# oscillation.net
KiCad netlist of a schematic drawn in Altium Designer
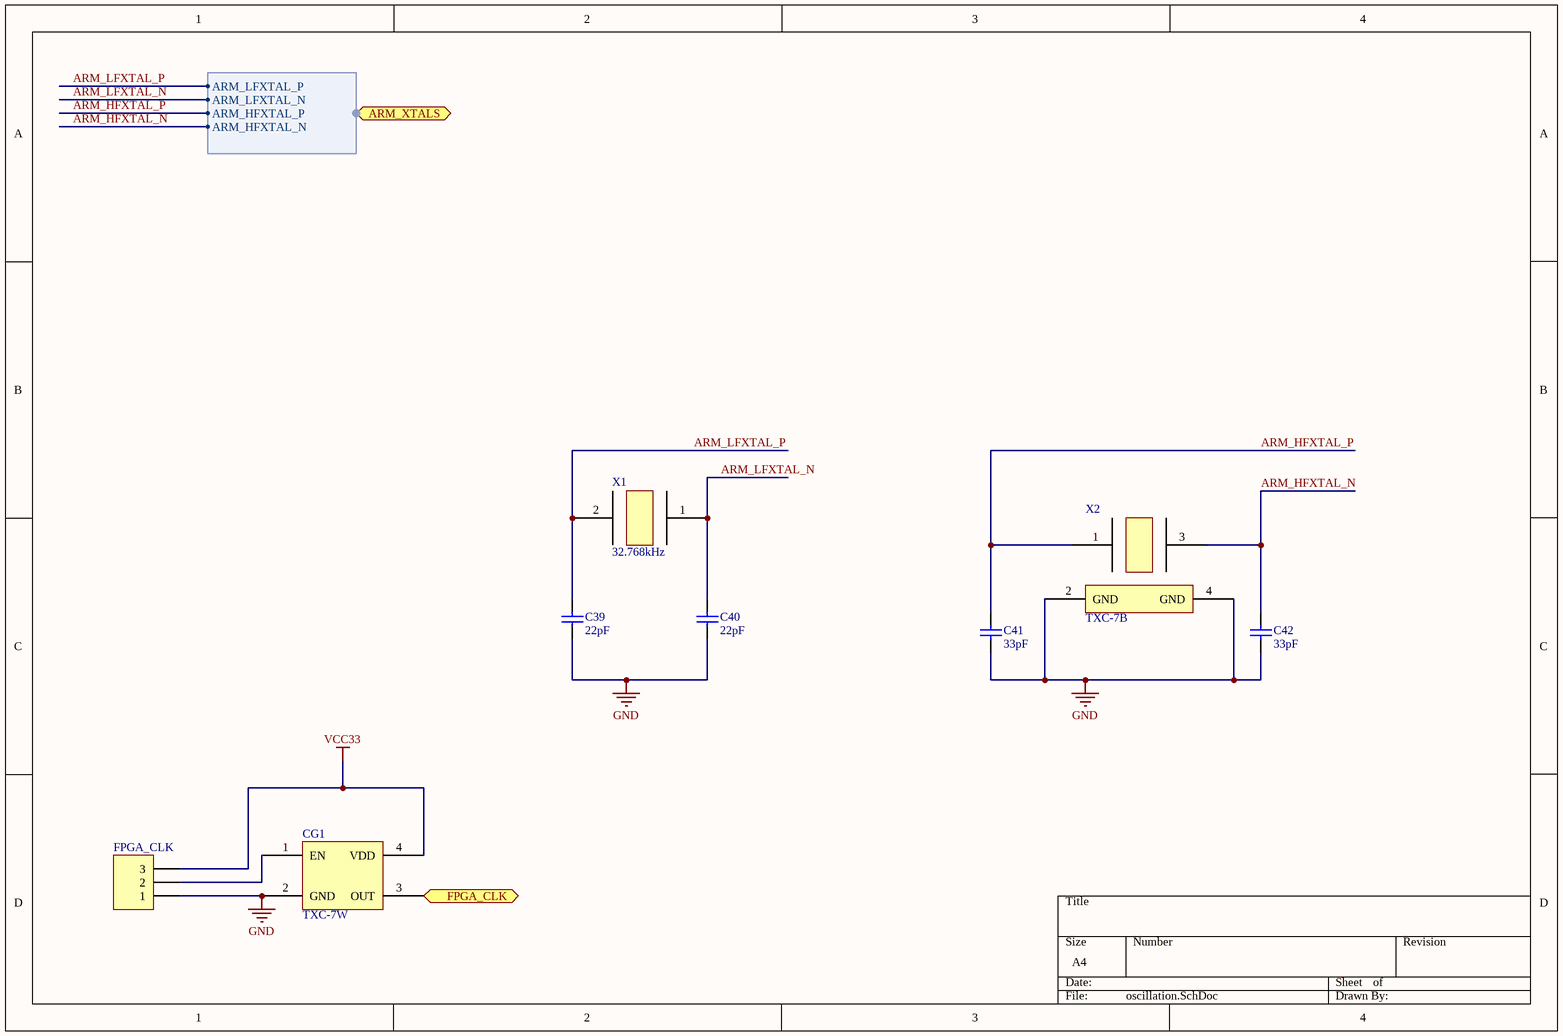
[diagram p0: oscillation.SchDoc]

(export (version "E")
  (design (tool "Eeschema 10.0.6"))
  (components
    (comp (ref "C39")
      (value "22pF")
      (footprint "CAPC0805(2012)75_L")
      (description "CAP 22pF 16V ±5% 0805 (2012 Metric) Thickness 0.75mm SMD")
      (fields (field (name "TOLERANCE") "±5%"))
      (libsource (lib "Altium Content Vault") (part "CMP-1036-01219-1"))
    )
    (comp (ref "C40")
      (value "22pF")
      (footprint "CAPC0805(2012)75_L")
      (description "CAP 22pF 16V ±5% 0805 (2012 Metric) Thickness 0.75mm SMD")
      (fields (field (name "TOLERANCE") "±5%"))
      (libsource (lib "Altium Content Vault") (part "CMP-1036-01219-1"))
    )
    (comp (ref "C41")
      (value "33pF")
      (footprint "CAPC0805(2012)75_L")
      (description "CAP 33pF 16V ±5% 0805 (2012 Metric) Thickness 0.75mm SMD")
      (fields (field (name "TOLERANCE") "±5%"))
      (libsource (lib "Altium Content Vault") (part "CMP-1036-01407-1"))
    )
    (comp (ref "C42")
      (value "33pF")
      (footprint "CAPC0805(2012)75_L")
      (description "CAP 33pF 16V ±5% 0805 (2012 Metric) Thickness 0.75mm SMD")
      (fields (field (name "TOLERANCE") "±5%"))
      (libsource (lib "Altium Content Vault") (part "CMP-1036-01407-1"))
    )
    (comp (ref "CG1")
      (value "TXC-7W")
      (footprint "TXC-7W")
      (libsource (lib "SR10S3V3_Schematic") (part "TXC-7W"))
    )
    (comp (ref "FPGA_CLK")
      (value "Header 3")
      (footprint "HDR1X3")
      (description "Header, 3-Pin")
      (fields (field (name "PUBLISHER") "Altium Limited"))
      (libsource (lib "Miscellaneous Connectors") (part "Header 3"))
    )
    (comp (ref "X1")
      (value "32.768kHz")
      (footprint "MC-306")
      (libsource (lib "SR10S3V3_Schematic") (part "MC-306"))
    )
    (comp (ref "X2")
      (value "TXC-7B")
      (footprint "TXC-7B")
      (libsource (lib "SR10S3V3_Schematic") (part "TXC-7B"))
    )
  )
  (nets
    (net (code "2") (name "/ARM_HFXTAL_N") (class "Default")
      (node (ref "C42") (pin "1") (pinfunction "1_1") (pintype "passive"))
      (node (ref "X2") (pin "3") (pinfunction "3_3") (pintype "passive"))
    )
    (net (code "3") (name "/ARM_HFXTAL_P") (class "Default")
      (node (ref "C41") (pin "1") (pinfunction "1_1") (pintype "passive"))
      (node (ref "X2") (pin "1") (pinfunction "1_1") (pintype "passive"))
    )
    (net (code "4") (name "/ARM_LFXTAL_N") (class "Default")
      (node (ref "C40") (pin "2") (pinfunction "2_2") (pintype "passive"))
      (node (ref "X1") (pin "1") (pinfunction "1_1") (pintype "passive"))
    )
    (net (code "5") (name "/ARM_LFXTAL_P") (class "Default")
      (node (ref "C39") (pin "2") (pinfunction "2_2") (pintype "passive"))
      (node (ref "X1") (pin "2") (pinfunction "2_2") (pintype "passive"))
    )
    (net (code "6") (name "/FPGA_CLK") (class "Default")
      (node (ref "CG1") (pin "3") (pinfunction "OUT_3") (pintype "passive"))
    )
    (net (code "8") (name "GND") (class "Default")
      (node (ref "C39") (pin "1") (pinfunction "1_1") (pintype "passive"))
      (node (ref "C40") (pin "1") (pinfunction "1_1") (pintype "passive"))
      (node (ref "C41") (pin "2") (pinfunction "2_2") (pintype "passive"))
      (node (ref "C42") (pin "2") (pinfunction "2_2") (pintype "passive"))
      (node (ref "CG1") (pin "2") (pinfunction "GND_2") (pintype "passive"))
      (node (ref "FPGA_CLK") (pin "1") (pinfunction "1_1") (pintype "passive"))
      (node (ref "X2") (pin "2") (pinfunction "GND_2") (pintype "passive"))
      (node (ref "X2") (pin "4") (pinfunction "GND_4") (pintype "passive"))
    )
    (net (code "9") (name "Net-(CG1-EN)") (class "Default")
      (node (ref "CG1") (pin "1") (pinfunction "EN_1") (pintype "passive"))
      (node (ref "FPGA_CLK") (pin "2") (pinfunction "2_2") (pintype "passive"))
    )
    (net (code "10") (name "VCC33") (class "Default")
      (node (ref "CG1") (pin "4") (pinfunction "VDD_4") (pintype "passive"))
      (node (ref "FPGA_CLK") (pin "3") (pinfunction "3_3") (pintype "passive"))
    )
  )
)
